# 15321_1.net
KiCad netlist of a schematic drawn in EAGLE
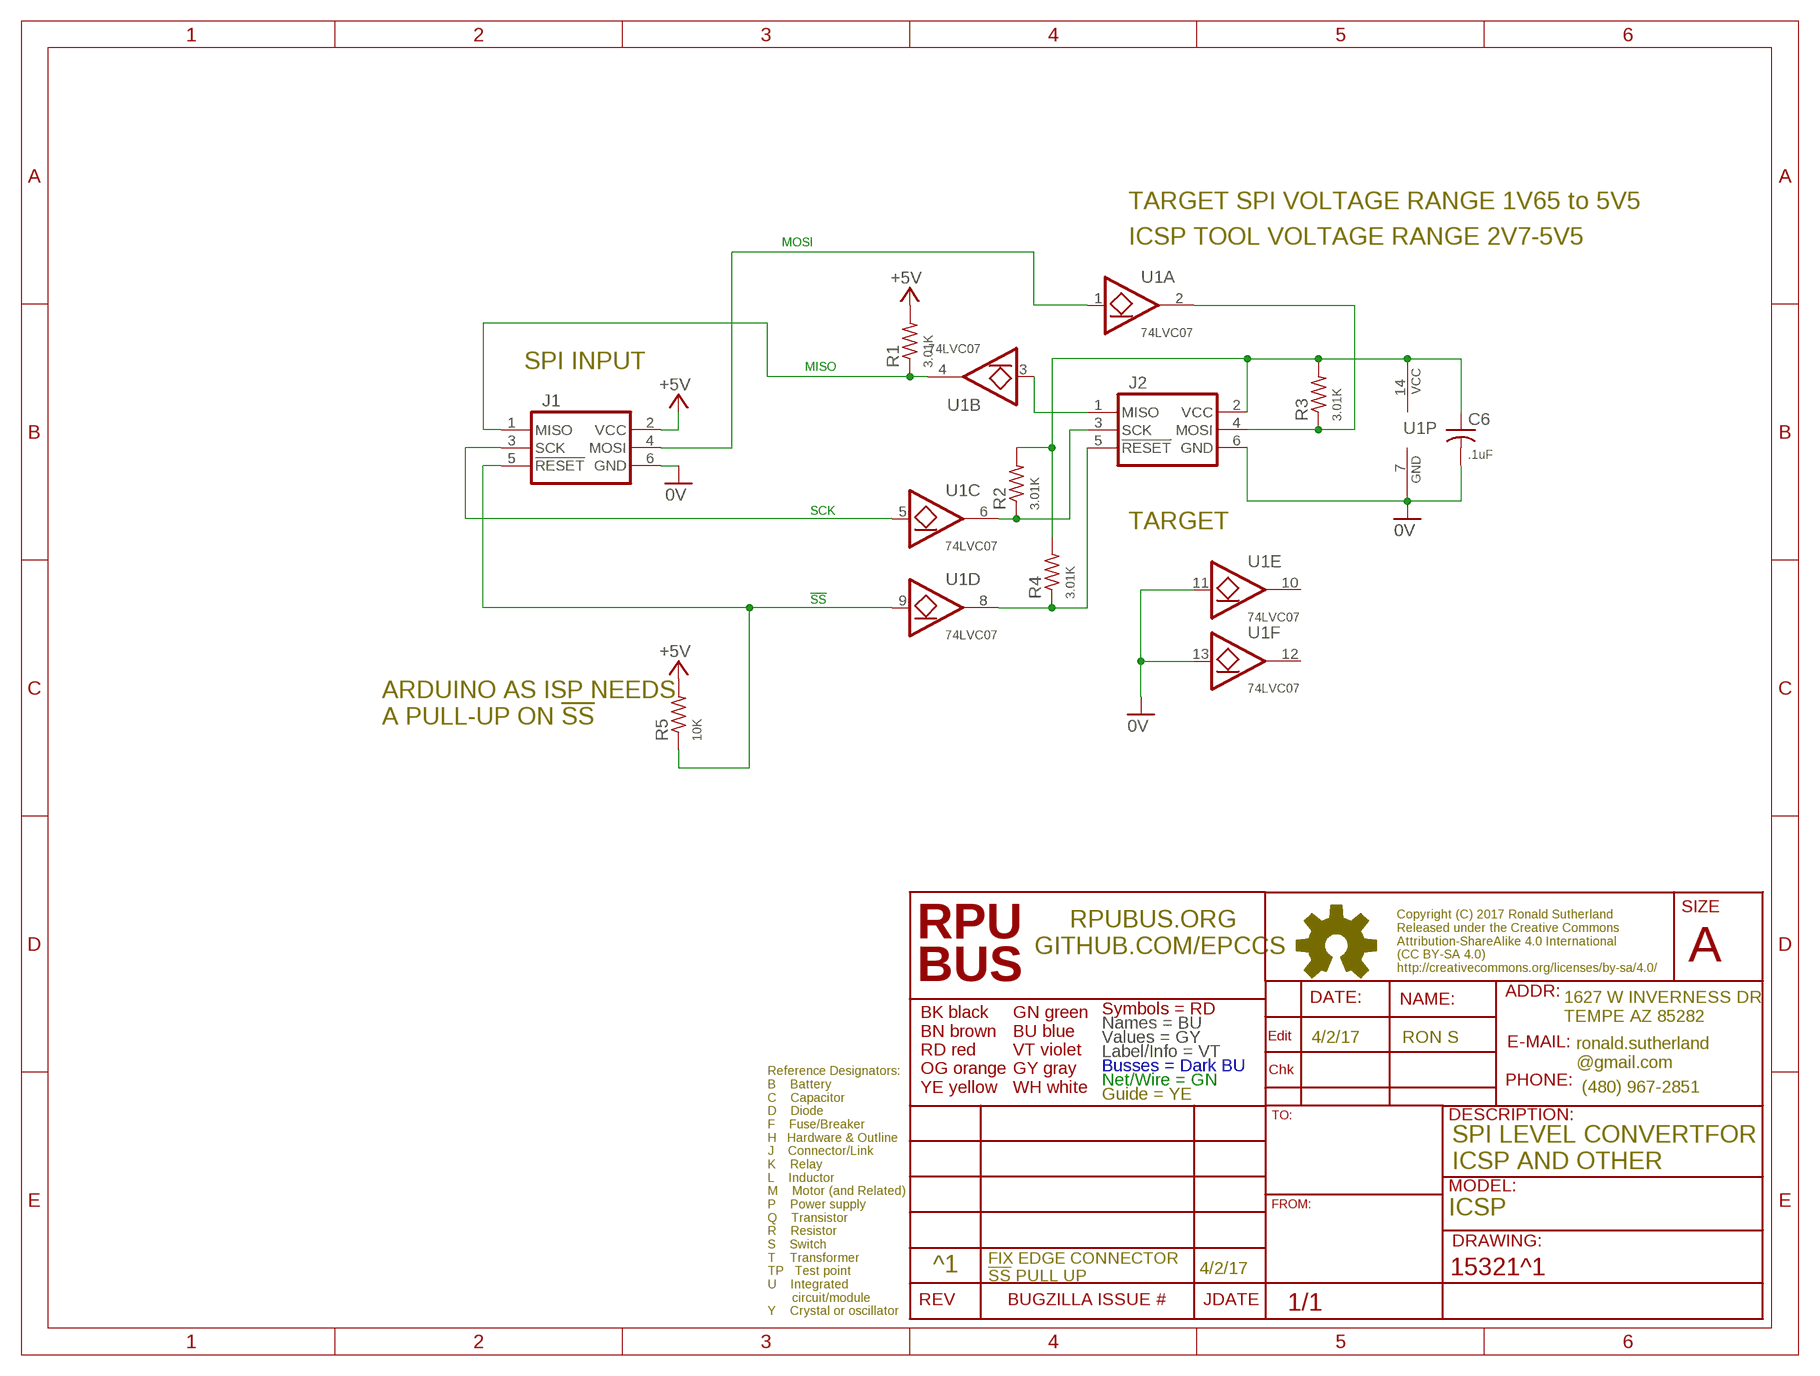
[diagram p0: schematic, sheet 1]

(export (version "E")
  (design (tool "Eeschema 10.0.6"))
  (components
    (comp (ref "C6")
      (value ".1uF")
      (footprint "eagle-import:C0603(1608)")
      (libsource (lib "eagle-import") (part "CC0603A"))
    )
    (comp (ref "J1")
      (value "ISP-SPIEDG")
      (footprint "eagle-import:ISP-EDG")
      (libsource (lib "eagle-import") (part "ISP-SPIEDG"))
    )
    (comp (ref "J2")
      (value "ISP-SPIEDG")
      (footprint "eagle-import:ISP-EDG")
      (libsource (lib "eagle-import") (part "ISP-SPIEDG"))
    )
    (comp (ref "R1")
      (value "3.01K")
      (footprint "eagle-import:C0805(2012)")
      (libsource (lib "eagle-import") (part "R0805"))
    )
    (comp (ref "R2")
      (value "3.01K")
      (footprint "eagle-import:C0805(2012)")
      (libsource (lib "eagle-import") (part "R0805"))
    )
    (comp (ref "R3")
      (value "3.01K")
      (footprint "eagle-import:C0805(2012)")
      (libsource (lib "eagle-import") (part "R0805"))
    )
    (comp (ref "R4")
      (value "3.01K")
      (footprint "eagle-import:C0805(2012)")
      (libsource (lib "eagle-import") (part "R0805"))
    )
    (comp (ref "R5")
      (value "10K")
      (footprint "eagle-import:C0805(2012)")
      (libsource (lib "eagle-import") (part "R0805"))
    )
    (comp (ref "U1")
      (value "74LVC07")
      (footprint "eagle-import:14SOIC")
      (libsource (lib "eagle-import") (part "7407D"))
    )
  )
  (nets
    (net (code "1") (name "+5V") (class "Default")
      (node (ref "J1") (pin "2") (pinfunction "VCC_2") (pintype "bidirectional"))
      (node (ref "R1") (pin "2") (pinfunction "2_2") (pintype "passive"))
      (node (ref "R5") (pin "2") (pinfunction "2_2") (pintype "passive"))
    )
    (net (code "2") (name "/MISO") (class "Default")
      (node (ref "J1") (pin "1") (pinfunction "MISO_1") (pintype "bidirectional"))
      (node (ref "R1") (pin "1") (pinfunction "1_1") (pintype "passive"))
      (node (ref "U1") (pin "4") (pinfunction "O_4") (pintype "open_collector"))
    )
    (net (code "3") (name "/MOSI") (class "Default")
      (node (ref "J1") (pin "4") (pinfunction "MOSI_4") (pintype "bidirectional"))
      (node (ref "U1") (pin "1") (pinfunction "I_1") (pintype "input"))
    )
    (net (code "4") (name "/SCK") (class "Default")
      (node (ref "J1") (pin "3") (pinfunction "SCK_3") (pintype "bidirectional"))
      (node (ref "U1") (pin "5") (pinfunction "I_5") (pintype "input"))
    )
    (net (code "5") (name "/~{SS}") (class "Default")
      (node (ref "J1") (pin "5") (pinfunction "~{RESET}_5") (pintype "bidirectional"))
      (node (ref "R5") (pin "1") (pinfunction "1_1") (pintype "passive"))
      (node (ref "U1") (pin "9") (pinfunction "I_9") (pintype "input"))
    )
    (net (code "6") (name "0V") (class "Default")
      (node (ref "C6") (pin "2") (pinfunction "2_2") (pintype "passive"))
      (node (ref "J1") (pin "6") (pinfunction "GND_6") (pintype "bidirectional"))
      (node (ref "J2") (pin "6") (pinfunction "GND_6") (pintype "bidirectional"))
      (node (ref "U1") (pin "11") (pinfunction "I_11") (pintype "input"))
      (node (ref "U1") (pin "13") (pinfunction "I_13") (pintype "input"))
      (node (ref "U1") (pin "7") (pinfunction "GND_7") (pintype "power_in"))
    )
    (net (code "7") (name "Net-(J2-MISO)") (class "Default")
      (node (ref "J2") (pin "1") (pinfunction "MISO_1") (pintype "bidirectional"))
      (node (ref "U1") (pin "3") (pinfunction "I_3") (pintype "input"))
    )
    (net (code "8") (name "Net-(J2-MOSI)") (class "Default")
      (node (ref "J2") (pin "4") (pinfunction "MOSI_4") (pintype "bidirectional"))
      (node (ref "R3") (pin "1") (pinfunction "1_1") (pintype "passive"))
      (node (ref "U1") (pin "2") (pinfunction "O_2") (pintype "open_collector"))
    )
    (net (code "9") (name "Net-(J2-SCK)") (class "Default")
      (node (ref "J2") (pin "3") (pinfunction "SCK_3") (pintype "bidirectional"))
      (node (ref "R2") (pin "1") (pinfunction "1_1") (pintype "passive"))
      (node (ref "U1") (pin "6") (pinfunction "O_6") (pintype "open_collector"))
    )
    (net (code "10") (name "Net-(J2-VCC)") (class "Default")
      (node (ref "C6") (pin "1") (pinfunction "1_1") (pintype "passive"))
      (node (ref "J2") (pin "2") (pinfunction "VCC_2") (pintype "bidirectional"))
      (node (ref "R2") (pin "2") (pinfunction "2_2") (pintype "passive"))
      (node (ref "R3") (pin "2") (pinfunction "2_2") (pintype "passive"))
      (node (ref "R4") (pin "2") (pinfunction "2_2") (pintype "passive"))
      (node (ref "U1") (pin "14") (pinfunction "VCC_14") (pintype "power_in"))
    )
    (net (code "11") (name "Net-(J2-~{RESET})") (class "Default")
      (node (ref "J2") (pin "5") (pinfunction "~{RESET}_5") (pintype "bidirectional"))
      (node (ref "R4") (pin "1") (pinfunction "1_1") (pintype "passive"))
      (node (ref "U1") (pin "8") (pinfunction "O_8") (pintype "open_collector"))
    )
    (net (code "12") (name "unconnected-(U1E-O-Pad10)") (class "Default")
      (node (ref "U1") (pin "10") (pinfunction "O_10") (pintype "open_collector"))
    )
    (net (code "13") (name "unconnected-(U1F-O-Pad12)") (class "Default")
      (node (ref "U1") (pin "12") (pinfunction "O_12") (pintype "open_collector"))
    )
  )
)
